# oao-001.net
KiCad netlist of a schematic drawn in EAGLE
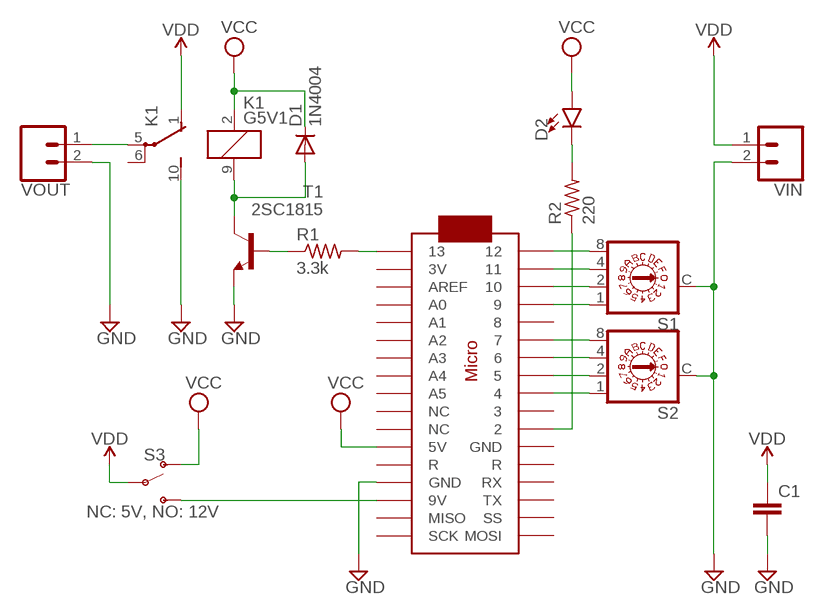
[diagram p0: schematic, sheet 1]

(export (version "E")
  (design (tool "Eeschema 10.0.6"))
  (components
    (comp (ref "C1")
      (value "C2,5-3")
      (footprint "eagle-import:C2.5-3")
      (libsource (lib "eagle-import") (part "C2,5-3"))
    )
    (comp (ref "D1")
      (value "1N4004")
      (footprint "eagle-import:DO41-10")
      (libsource (lib "eagle-import") (part "1N4004"))
    )
    (comp (ref "D2")
      (value "LED-3MM-NO_SILK")
      (footprint "eagle-import:LED_3MM-NS")
      (libsource (lib "eagle-import") (part "LED-3MM-NO_SILK"))
    )
    (comp (ref "K1")
      (value "G5V1")
      (footprint "eagle-import:G5V1")
      (fields (field (name "MPN") "G5V-1-DC24"))
      (libsource (lib "eagle-import") (part "G5V1"))
    )
    (comp (ref "R1")
      (value "3.3k")
      (footprint "eagle-import:0204_5")
      (libsource (lib "eagle-import") (part "R-US_0204/5"))
    )
    (comp (ref "R2")
      (value "220")
      (footprint "eagle-import:0204_5")
      (libsource (lib "eagle-import") (part "R-US_0204/5"))
    )
    (comp (ref "S1")
      (value "A1353HEX")
      (footprint "eagle-import:A1353HEX")
      (libsource (lib "eagle-import") (part "A1353HEX"))
    )
    (comp (ref "S2")
      (value "A1353HEX")
      (footprint "eagle-import:A1353HEX")
      (libsource (lib "eagle-import") (part "A1353HEX"))
    )
    (comp (ref "S3")
      (value "NC: 5V, NO: 12V")
      (footprint "eagle-import:SWITCH_SPDT_PTH_11.6X4.0MM")
      (libsource (lib "eagle-import") (part "SWITCH-SPDT-PTH-11.6X4.0MM"))
    )
    (comp (ref "T1")
      (value "2SC1815")
      (footprint "eagle-import:TO92-ECB")
      (libsource (lib "eagle-import") (part "2SC1815"))
    )
    (comp (ref "U$1")
      (value "ARDUINOMICRO")
      (footprint "eagle-import:ARDUINOMICRO")
      (libsource (lib "eagle-import") (part "ARDUINOMICRO"))
    )
    (comp (ref "VIN")
      (value "CONN_02LOCK")
      (footprint "eagle-import:1X02_LOCK")
      (libsource (lib "eagle-import") (part "CONN_02LOCK"))
    )
    (comp (ref "VOUT")
      (value "CONN_02LOCK")
      (footprint "eagle-import:1X02_LOCK")
      (libsource (lib "eagle-import") (part "CONN_02LOCK"))
    )
  )
  (nets
    (net (code "1") (name "GND") (class "Default")
      (node (ref "C1") (pin "2") (pinfunction "2_2") (pintype "passive"))
      (node (ref "K1") (pin "10") (pinfunction "S_10") (pintype "passive"))
      (node (ref "S1") (pin "C") (pinfunction "C_C") (pintype "passive"))
      (node (ref "S2") (pin "C") (pinfunction "C_C") (pintype "passive"))
      (node (ref "T1") (pin "E") (pinfunction "E_E") (pintype "passive"))
      (node (ref "U$1") (pin "P$12") (pinfunction "GND_P$12") (pintype "bidirectional"))
      (node (ref "VIN") (pin "2") (pinfunction "2_2") (pintype "passive"))
      (node (ref "VOUT") (pin "2") (pinfunction "2_2") (pintype "passive"))
    )
    (net (code "2") (name "Net-(D2-C)") (class "Default")
      (node (ref "D2") (pin "K") (pinfunction "C_K") (pintype "passive"))
      (node (ref "R2") (pin "2") (pinfunction "2_2") (pintype "passive"))
    )
    (net (code "3") (name "Net-(K1A-2)") (class "Default")
      (node (ref "D1") (pin "A") (pinfunction "A_A") (pintype "passive"))
      (node (ref "K1") (pin "9") (pinfunction "2_9") (pintype "passive"))
      (node (ref "T1") (pin "C") (pinfunction "C_C") (pintype "passive"))
    )
    (net (code "4") (name "Net-(K1B-P-Pad5)") (class "Default")
      (node (ref "K1") (pin "5") (pinfunction "P_5") (pintype "passive"))
      (node (ref "VOUT") (pin "1") (pinfunction "1_1") (pintype "passive"))
    )
    (net (code "5") (name "Net-(R1-Pad1)") (class "Default")
      (node (ref "R1") (pin "1") (pinfunction "1_1") (pintype "passive"))
      (node (ref "T1") (pin "B") (pinfunction "B_B") (pintype "passive"))
    )
    (net (code "6") (name "Net-(S3-S)") (class "Default")
      (node (ref "S3") (pin "3") (pinfunction "S_3") (pintype "passive"))
      (node (ref "U$1") (pin "P$20") (pinfunction "9V_P$20") (pintype "bidirectional"))
    )
    (net (code "7") (name "Net-(U$1-2)") (class "Default")
      (node (ref "R2") (pin "1") (pinfunction "1_1") (pintype "passive"))
      (node (ref "U$1") (pin "P$11") (pinfunction "2_P$11") (pintype "bidirectional"))
    )
    (net (code "8") (name "Net-(U$1-4)") (class "Default")
      (node (ref "S2") (pin "1") (pinfunction "1_1") (pintype "passive"))
      (node (ref "U$1") (pin "P$9") (pinfunction "4_P$9") (pintype "bidirectional"))
    )
    (net (code "9") (name "Net-(U$1-5)") (class "Default")
      (node (ref "S2") (pin "2") (pinfunction "2_2") (pintype "passive"))
      (node (ref "U$1") (pin "P$8") (pinfunction "5_P$8") (pintype "bidirectional"))
    )
    (net (code "10") (name "Net-(U$1-6)") (class "Default")
      (node (ref "S2") (pin "4") (pinfunction "4_4") (pintype "passive"))
      (node (ref "U$1") (pin "P$7") (pinfunction "6_P$7") (pintype "bidirectional"))
    )
    (net (code "11") (name "Net-(U$1-7)") (class "Default")
      (node (ref "S2") (pin "8") (pinfunction "8_8") (pintype "passive"))
      (node (ref "U$1") (pin "P$6") (pinfunction "7_P$6") (pintype "bidirectional"))
    )
    (net (code "12") (name "Net-(U$1-9)") (class "Default")
      (node (ref "S1") (pin "1") (pinfunction "1_1") (pintype "passive"))
      (node (ref "U$1") (pin "P$4") (pinfunction "9_P$4") (pintype "bidirectional"))
    )
    (net (code "13") (name "Net-(U$1-10)") (class "Default")
      (node (ref "S1") (pin "2") (pinfunction "2_2") (pintype "passive"))
      (node (ref "U$1") (pin "P$3") (pinfunction "10_P$3") (pintype "bidirectional"))
    )
    (net (code "14") (name "Net-(U$1-11)") (class "Default")
      (node (ref "S1") (pin "4") (pinfunction "4_4") (pintype "passive"))
      (node (ref "U$1") (pin "P$2") (pinfunction "11_P$2") (pintype "bidirectional"))
    )
    (net (code "15") (name "Net-(U$1-12)") (class "Default")
      (node (ref "S1") (pin "8") (pinfunction "8_8") (pintype "passive"))
      (node (ref "U$1") (pin "P$1") (pinfunction "12_P$1") (pintype "bidirectional"))
    )
    (net (code "16") (name "Net-(U$1-13)") (class "Default")
      (node (ref "R1") (pin "2") (pinfunction "2_2") (pintype "passive"))
      (node (ref "U$1") (pin "P$34") (pinfunction "13_P$34") (pintype "bidirectional"))
    )
    (net (code "17") (name "VCC") (class "Default")
      (node (ref "D1") (pin "C") (pinfunction "C_C") (pintype "passive"))
      (node (ref "D2") (pin "A") (pinfunction "A_A") (pintype "passive"))
      (node (ref "K1") (pin "2") (pinfunction "1_2") (pintype "passive"))
      (node (ref "S3") (pin "1") (pinfunction "O_1") (pintype "passive"))
      (node (ref "U$1") (pin "P$23") (pinfunction "5V_P$23") (pintype "bidirectional"))
    )
    (net (code "18") (name "VDD") (class "Default")
      (node (ref "C1") (pin "1") (pinfunction "1_1") (pintype "passive"))
      (node (ref "K1") (pin "1") (pinfunction "O_1") (pintype "passive"))
      (node (ref "S3") (pin "2") (pinfunction "P_2") (pintype "passive"))
      (node (ref "VIN") (pin "1") (pinfunction "1_1") (pintype "passive"))
    )
    (net (code "19") (name "unconnected-(K1B-P-Pad6)") (class "Default")
      (node (ref "K1") (pin "6") (pinfunction "P_6") (pintype "passive"))
    )
    (net (code "20") (name "unconnected-(U$1-3-PadP$10)") (class "Default")
      (node (ref "U$1") (pin "P$10") (pinfunction "3_P$10") (pintype "bidirectional"))
    )
    (net (code "21") (name "unconnected-(U$1-3V-PadP$33)") (class "Default")
      (node (ref "U$1") (pin "P$33") (pinfunction "3V_P$33") (pintype "bidirectional"))
    )
    (net (code "22") (name "unconnected-(U$1-8-PadP$5)") (class "Default")
      (node (ref "U$1") (pin "P$5") (pinfunction "8_P$5") (pintype "bidirectional"))
    )
    (net (code "23") (name "unconnected-(U$1-A0-PadP$31)") (class "Default")
      (node (ref "U$1") (pin "P$31") (pinfunction "A0_P$31") (pintype "bidirectional"))
    )
    (net (code "24") (name "unconnected-(U$1-A1-PadP$30)") (class "Default")
      (node (ref "U$1") (pin "P$30") (pinfunction "A1_P$30") (pintype "bidirectional"))
    )
    (net (code "25") (name "unconnected-(U$1-A2-PadP$29)") (class "Default")
      (node (ref "U$1") (pin "P$29") (pinfunction "A2_P$29") (pintype "bidirectional"))
    )
    (net (code "26") (name "unconnected-(U$1-A3-PadP$28)") (class "Default")
      (node (ref "U$1") (pin "P$28") (pinfunction "A3_P$28") (pintype "bidirectional"))
    )
    (net (code "27") (name "unconnected-(U$1-A4-PadP$27)") (class "Default")
      (node (ref "U$1") (pin "P$27") (pinfunction "A4_P$27") (pintype "bidirectional"))
    )
    (net (code "28") (name "unconnected-(U$1-A5-PadP$26)") (class "Default")
      (node (ref "U$1") (pin "P$26") (pinfunction "A5_P$26") (pintype "bidirectional"))
    )
    (net (code "29") (name "unconnected-(U$1-AREF-PadP$32)") (class "Default")
      (node (ref "U$1") (pin "P$32") (pinfunction "AREF_P$32") (pintype "bidirectional"))
    )
    (net (code "30") (name "unconnected-(U$1-GND-PadP$21)") (class "Default")
      (node (ref "U$1") (pin "P$21") (pinfunction "GND_P$21") (pintype "bidirectional"))
    )
    (net (code "31") (name "unconnected-(U$1-MISO-PadP$19)") (class "Default")
      (node (ref "U$1") (pin "P$19") (pinfunction "MISO_P$19") (pintype "bidirectional"))
    )
    (net (code "32") (name "unconnected-(U$1-MOSI-PadP$17)") (class "Default")
      (node (ref "U$1") (pin "P$17") (pinfunction "MOSI_P$17") (pintype "bidirectional"))
    )
    (net (code "33") (name "unconnected-(U$1-NC-PadP$24)") (class "Default")
      (node (ref "U$1") (pin "P$24") (pinfunction "NC_P$24") (pintype "bidirectional"))
    )
    (net (code "34") (name "unconnected-(U$1-NC-PadP$25)") (class "Default")
      (node (ref "U$1") (pin "P$25") (pinfunction "NC_P$25") (pintype "bidirectional"))
    )
    (net (code "35") (name "unconnected-(U$1-R-PadP$13)") (class "Default")
      (node (ref "U$1") (pin "P$13") (pinfunction "R_P$13") (pintype "bidirectional"))
    )
    (net (code "36") (name "unconnected-(U$1-R-PadP$22)") (class "Default")
      (node (ref "U$1") (pin "P$22") (pinfunction "R_P$22") (pintype "bidirectional"))
    )
    (net (code "37") (name "unconnected-(U$1-RX-PadP$14)") (class "Default")
      (node (ref "U$1") (pin "P$14") (pinfunction "RX_P$14") (pintype "bidirectional"))
    )
    (net (code "38") (name "unconnected-(U$1-SCK-PadP$18)") (class "Default")
      (node (ref "U$1") (pin "P$18") (pinfunction "SCK_P$18") (pintype "bidirectional"))
    )
    (net (code "39") (name "unconnected-(U$1-SS-PadP$16)") (class "Default")
      (node (ref "U$1") (pin "P$16") (pinfunction "SS_P$16") (pintype "bidirectional"))
    )
    (net (code "40") (name "unconnected-(U$1-TX-PadP$15)") (class "Default")
      (node (ref "U$1") (pin "P$15") (pinfunction "TX_P$15") (pintype "bidirectional"))
    )
  )
)
